# InterfacesB_SHIFTER_LEDS.net
KiCad netlist of a schematic drawn in Altium Designer
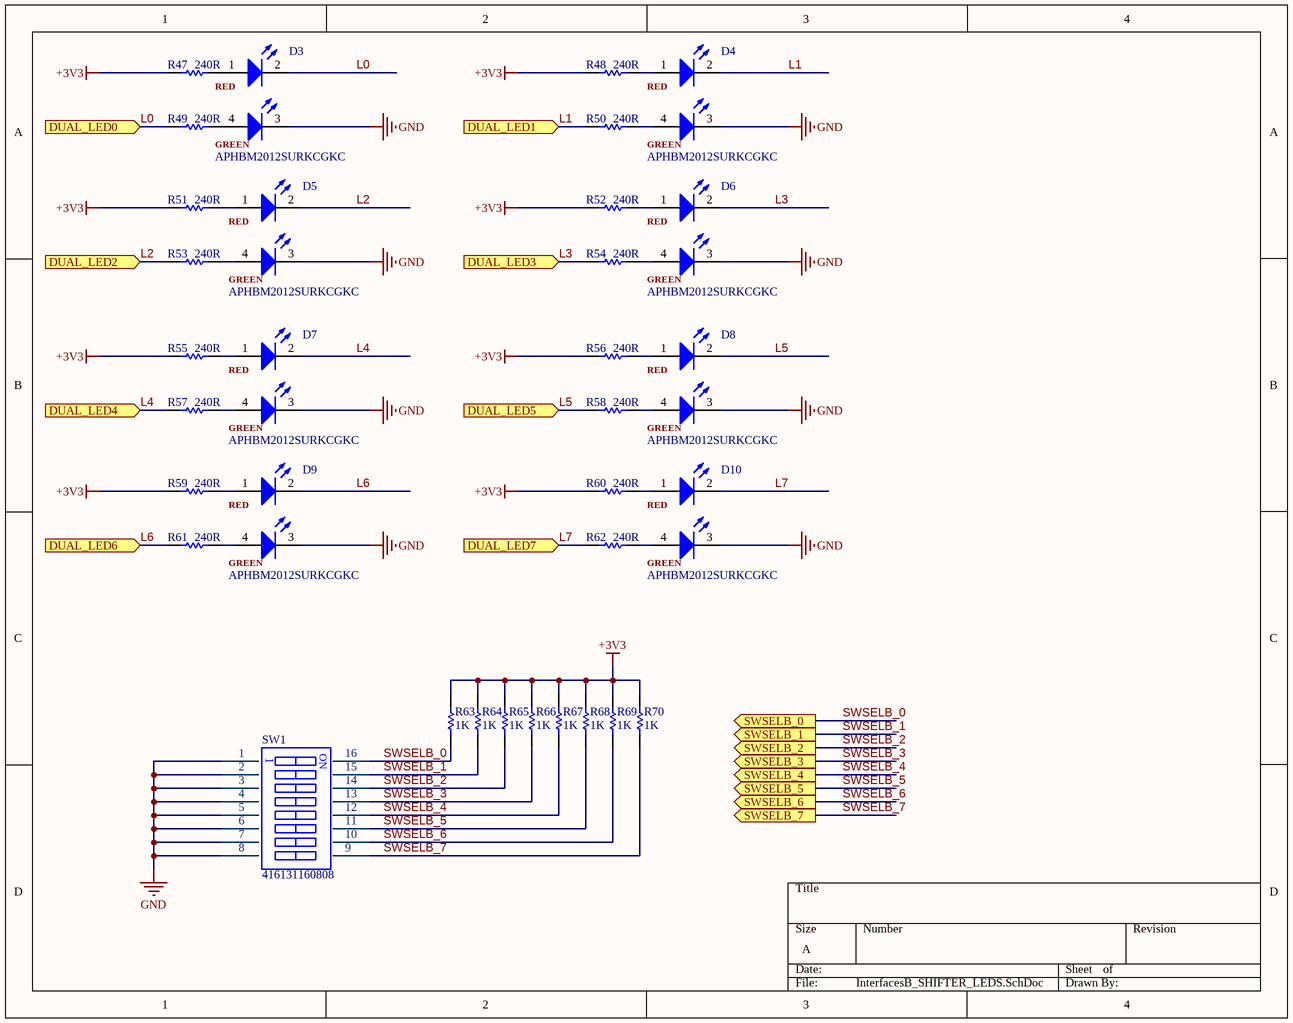
[diagram p0: InterfacesB_SHIFTER_LEDS.SchDoc]

(export (version "E")
  (design (tool "Eeschema 10.0.6"))
  (components
    (comp (ref "D3")
      (value "APHBM2012SURKCGKC")
      (footprint "APHBM2012SURKCGKC")
      (libsource (lib "AdapterLib") (part "APHBM2012SURKCGKC"))
    )
    (comp (ref "D4")
      (value "APHBM2012SURKCGKC")
      (footprint "APHBM2012SURKCGKC")
      (libsource (lib "AdapterLib") (part "APHBM2012SURKCGKC"))
    )
    (comp (ref "D5")
      (value "APHBM2012SURKCGKC")
      (footprint "APHBM2012SURKCGKC")
      (libsource (lib "AdapterLib") (part "APHBM2012SURKCGKC"))
    )
    (comp (ref "D6")
      (value "APHBM2012SURKCGKC")
      (footprint "APHBM2012SURKCGKC")
      (libsource (lib "AdapterLib") (part "APHBM2012SURKCGKC"))
    )
    (comp (ref "D7")
      (value "APHBM2012SURKCGKC")
      (footprint "APHBM2012SURKCGKC")
      (libsource (lib "AdapterLib") (part "APHBM2012SURKCGKC"))
    )
    (comp (ref "D8")
      (value "APHBM2012SURKCGKC")
      (footprint "APHBM2012SURKCGKC")
      (libsource (lib "AdapterLib") (part "APHBM2012SURKCGKC"))
    )
    (comp (ref "D9")
      (value "APHBM2012SURKCGKC")
      (footprint "APHBM2012SURKCGKC")
      (libsource (lib "AdapterLib") (part "APHBM2012SURKCGKC"))
    )
    (comp (ref "D10")
      (value "APHBM2012SURKCGKC")
      (footprint "APHBM2012SURKCGKC")
      (libsource (lib "AdapterLib") (part "APHBM2012SURKCGKC"))
    )
    (comp (ref "R47")
      (value "240R")
      (footprint "RES_0805")
      (fields (field (name "Comment") "RES_0805"))
      (libsource (lib "AdapterLib") (part "RES_0805"))
    )
    (comp (ref "R48")
      (value "240R")
      (footprint "RES_0805")
      (fields (field (name "Comment") "RES_0805"))
      (libsource (lib "AdapterLib") (part "RES_0805"))
    )
    (comp (ref "R49")
      (value "240R")
      (footprint "RES_0805")
      (fields (field (name "Comment") "RES_0805"))
      (libsource (lib "AdapterLib") (part "RES_0805"))
    )
    (comp (ref "R50")
      (value "240R")
      (footprint "RES_0805")
      (fields (field (name "Comment") "RES_0805"))
      (libsource (lib "AdapterLib") (part "RES_0805"))
    )
    (comp (ref "R51")
      (value "240R")
      (footprint "RES_0805")
      (fields (field (name "Comment") "RES_0805"))
      (libsource (lib "AdapterLib") (part "RES_0805"))
    )
    (comp (ref "R52")
      (value "240R")
      (footprint "RES_0805")
      (fields (field (name "Comment") "RES_0805"))
      (libsource (lib "AdapterLib") (part "RES_0805"))
    )
    (comp (ref "R53")
      (value "240R")
      (footprint "RES_0805")
      (fields (field (name "Comment") "RES_0805"))
      (libsource (lib "AdapterLib") (part "RES_0805"))
    )
    (comp (ref "R54")
      (value "240R")
      (footprint "RES_0805")
      (fields (field (name "Comment") "RES_0805"))
      (libsource (lib "AdapterLib") (part "RES_0805"))
    )
    (comp (ref "R55")
      (value "240R")
      (footprint "RES_0805")
      (fields (field (name "Comment") "RES_0805"))
      (libsource (lib "AdapterLib") (part "RES_0805"))
    )
    (comp (ref "R56")
      (value "240R")
      (footprint "RES_0805")
      (fields (field (name "Comment") "RES_0805"))
      (libsource (lib "AdapterLib") (part "RES_0805"))
    )
    (comp (ref "R57")
      (value "240R")
      (footprint "RES_0805")
      (fields (field (name "Comment") "RES_0805"))
      (libsource (lib "AdapterLib") (part "RES_0805"))
    )
    (comp (ref "R58")
      (value "240R")
      (footprint "RES_0805")
      (fields (field (name "Comment") "RES_0805"))
      (libsource (lib "AdapterLib") (part "RES_0805"))
    )
    (comp (ref "R59")
      (value "240R")
      (footprint "RES_0805")
      (fields (field (name "Comment") "RES_0805"))
      (libsource (lib "AdapterLib") (part "RES_0805"))
    )
    (comp (ref "R60")
      (value "240R")
      (footprint "RES_0805")
      (fields (field (name "Comment") "RES_0805"))
      (libsource (lib "AdapterLib") (part "RES_0805"))
    )
    (comp (ref "R61")
      (value "240R")
      (footprint "RES_0805")
      (fields (field (name "Comment") "RES_0805"))
      (libsource (lib "AdapterLib") (part "RES_0805"))
    )
    (comp (ref "R62")
      (value "240R")
      (footprint "RES_0805")
      (fields (field (name "Comment") "RES_0805"))
      (libsource (lib "AdapterLib") (part "RES_0805"))
    )
    (comp (ref "R63")
      (value "1K")
      (footprint "RES_0805")
      (fields (field (name "Comment") "RES_0805"))
      (libsource (lib "AdapterLib") (part "RES_0805"))
    )
    (comp (ref "R64")
      (value "1K")
      (footprint "RES_0805")
      (fields (field (name "Comment") "RES_0805"))
      (libsource (lib "AdapterLib") (part "RES_0805"))
    )
    (comp (ref "R65")
      (value "1K")
      (footprint "RES_0805")
      (fields (field (name "Comment") "RES_0805"))
      (libsource (lib "AdapterLib") (part "RES_0805"))
    )
    (comp (ref "R66")
      (value "1K")
      (footprint "RES_0805")
      (fields (field (name "Comment") "RES_0805"))
      (libsource (lib "AdapterLib") (part "RES_0805"))
    )
    (comp (ref "R67")
      (value "1K")
      (footprint "RES_0805")
      (fields (field (name "Comment") "RES_0805"))
      (libsource (lib "AdapterLib") (part "RES_0805"))
    )
    (comp (ref "R68")
      (value "1K")
      (footprint "RES_0805")
      (fields (field (name "Comment") "RES_0805"))
      (libsource (lib "AdapterLib") (part "RES_0805"))
    )
    (comp (ref "R69")
      (value "1K")
      (footprint "RES_0805")
      (fields (field (name "Comment") "RES_0805"))
      (libsource (lib "AdapterLib") (part "RES_0805"))
    )
    (comp (ref "R70")
      (value "1K")
      (footprint "RES_0805")
      (fields (field (name "Comment") "RES_0805"))
      (libsource (lib "AdapterLib") (part "RES_0805"))
    )
    (comp (ref "SW1")
      (value "416131160808")
      (footprint "416131160808")
      (description "8 POS DIP SW SMD")
      (libsource (lib "AdapterLib") (part "416131160808"))
    )
  )
  (nets
    (net (code "1") (name "+3V3") (class "Default")
      (node (ref "R47") (pin "2") (pinfunction "2_2") (pintype "passive"))
      (node (ref "R48") (pin "2") (pinfunction "2_2") (pintype "passive"))
      (node (ref "R51") (pin "2") (pinfunction "2_2") (pintype "passive"))
      (node (ref "R52") (pin "2") (pinfunction "2_2") (pintype "passive"))
      (node (ref "R55") (pin "2") (pinfunction "2_2") (pintype "passive"))
      (node (ref "R56") (pin "2") (pinfunction "2_2") (pintype "passive"))
      (node (ref "R59") (pin "2") (pinfunction "2_2") (pintype "passive"))
      (node (ref "R60") (pin "2") (pinfunction "2_2") (pintype "passive"))
      (node (ref "R63") (pin "2") (pinfunction "2_2") (pintype "passive"))
      (node (ref "R64") (pin "2") (pinfunction "2_2") (pintype "passive"))
      (node (ref "R65") (pin "2") (pinfunction "2_2") (pintype "passive"))
      (node (ref "R66") (pin "2") (pinfunction "2_2") (pintype "passive"))
      (node (ref "R67") (pin "2") (pinfunction "2_2") (pintype "passive"))
      (node (ref "R68") (pin "2") (pinfunction "2_2") (pintype "passive"))
      (node (ref "R69") (pin "2") (pinfunction "2_2") (pintype "passive"))
      (node (ref "R70") (pin "2") (pinfunction "2_2") (pintype "passive"))
    )
    (net (code "2") (name "/L0") (class "Default")
      (node (ref "D3") (pin "2") (pinfunction "2_2") (pintype "passive"))
      (node (ref "R49") (pin "2") (pinfunction "2_2") (pintype "passive"))
    )
    (net (code "3") (name "/L1") (class "Default")
      (node (ref "D4") (pin "2") (pinfunction "2_2") (pintype "passive"))
      (node (ref "R50") (pin "2") (pinfunction "2_2") (pintype "passive"))
    )
    (net (code "4") (name "/L2") (class "Default")
      (node (ref "D5") (pin "2") (pinfunction "2_2") (pintype "passive"))
      (node (ref "R53") (pin "2") (pinfunction "2_2") (pintype "passive"))
    )
    (net (code "5") (name "/L3") (class "Default")
      (node (ref "D6") (pin "2") (pinfunction "2_2") (pintype "passive"))
      (node (ref "R54") (pin "2") (pinfunction "2_2") (pintype "passive"))
    )
    (net (code "6") (name "/L4") (class "Default")
      (node (ref "D7") (pin "2") (pinfunction "2_2") (pintype "passive"))
      (node (ref "R57") (pin "2") (pinfunction "2_2") (pintype "passive"))
    )
    (net (code "7") (name "/L5") (class "Default")
      (node (ref "D8") (pin "2") (pinfunction "2_2") (pintype "passive"))
      (node (ref "R58") (pin "2") (pinfunction "2_2") (pintype "passive"))
    )
    (net (code "8") (name "/L6") (class "Default")
      (node (ref "D9") (pin "2") (pinfunction "2_2") (pintype "passive"))
      (node (ref "R61") (pin "2") (pinfunction "2_2") (pintype "passive"))
    )
    (net (code "9") (name "/L7") (class "Default")
      (node (ref "D10") (pin "2") (pinfunction "2_2") (pintype "passive"))
      (node (ref "R62") (pin "2") (pinfunction "2_2") (pintype "passive"))
    )
    (net (code "10") (name "/SWSELB_0") (class "Default")
      (node (ref "R63") (pin "1") (pinfunction "1_1") (pintype "passive"))
      (node (ref "SW1") (pin "16") (pintype "passive"))
    )
    (net (code "11") (name "/SWSELB_1") (class "Default")
      (node (ref "R64") (pin "1") (pinfunction "1_1") (pintype "passive"))
      (node (ref "SW1") (pin "15") (pintype "passive"))
    )
    (net (code "12") (name "/SWSELB_2") (class "Default")
      (node (ref "R65") (pin "1") (pinfunction "1_1") (pintype "passive"))
      (node (ref "SW1") (pin "14") (pintype "passive"))
    )
    (net (code "13") (name "/SWSELB_3") (class "Default")
      (node (ref "R66") (pin "1") (pinfunction "1_1") (pintype "passive"))
      (node (ref "SW1") (pin "13") (pintype "passive"))
    )
    (net (code "14") (name "/SWSELB_4") (class "Default")
      (node (ref "R67") (pin "1") (pinfunction "1_1") (pintype "passive"))
      (node (ref "SW1") (pin "12") (pintype "passive"))
    )
    (net (code "15") (name "/SWSELB_5") (class "Default")
      (node (ref "R68") (pin "1") (pinfunction "1_1") (pintype "passive"))
      (node (ref "SW1") (pin "11") (pintype "passive"))
    )
    (net (code "16") (name "/SWSELB_6") (class "Default")
      (node (ref "R69") (pin "1") (pinfunction "1_1") (pintype "passive"))
      (node (ref "SW1") (pin "10") (pintype "passive"))
    )
    (net (code "17") (name "/SWSELB_7") (class "Default")
      (node (ref "R70") (pin "1") (pinfunction "1_1") (pintype "passive"))
      (node (ref "SW1") (pin "9") (pintype "passive"))
    )
    (net (code "18") (name "GND") (class "Default")
      (node (ref "D10") (pin "3") (pinfunction "3_3") (pintype "passive"))
      (node (ref "D3") (pin "3") (pinfunction "3_3") (pintype "passive"))
      (node (ref "D4") (pin "3") (pinfunction "3_3") (pintype "passive"))
      (node (ref "D5") (pin "3") (pinfunction "3_3") (pintype "passive"))
      (node (ref "D6") (pin "3") (pinfunction "3_3") (pintype "passive"))
      (node (ref "D7") (pin "3") (pinfunction "3_3") (pintype "passive"))
      (node (ref "D8") (pin "3") (pinfunction "3_3") (pintype "passive"))
      (node (ref "D9") (pin "3") (pinfunction "3_3") (pintype "passive"))
      (node (ref "SW1") (pin "1") (pintype "passive"))
      (node (ref "SW1") (pin "2") (pintype "passive"))
      (node (ref "SW1") (pin "3") (pintype "passive"))
      (node (ref "SW1") (pin "4") (pintype "passive"))
      (node (ref "SW1") (pin "5") (pintype "passive"))
      (node (ref "SW1") (pin "6") (pintype "passive"))
      (node (ref "SW1") (pin "7") (pintype "passive"))
      (node (ref "SW1") (pin "8") (pintype "passive"))
    )
    (net (code "19") (name "Net-(D3-Pad1)") (class "Default")
      (node (ref "D3") (pin "1") (pinfunction "1_1") (pintype "passive"))
      (node (ref "R47") (pin "1") (pinfunction "1_1") (pintype "passive"))
    )
    (net (code "20") (name "Net-(D3-Pad4)") (class "Default")
      (node (ref "D3") (pin "4") (pinfunction "4_4") (pintype "passive"))
      (node (ref "R49") (pin "1") (pinfunction "1_1") (pintype "passive"))
    )
    (net (code "21") (name "Net-(D4-Pad1)") (class "Default")
      (node (ref "D4") (pin "1") (pinfunction "1_1") (pintype "passive"))
      (node (ref "R48") (pin "1") (pinfunction "1_1") (pintype "passive"))
    )
    (net (code "22") (name "Net-(D4-Pad4)") (class "Default")
      (node (ref "D4") (pin "4") (pinfunction "4_4") (pintype "passive"))
      (node (ref "R50") (pin "1") (pinfunction "1_1") (pintype "passive"))
    )
    (net (code "23") (name "Net-(D5-Pad1)") (class "Default")
      (node (ref "D5") (pin "1") (pinfunction "1_1") (pintype "passive"))
      (node (ref "R51") (pin "1") (pinfunction "1_1") (pintype "passive"))
    )
    (net (code "24") (name "Net-(D5-Pad4)") (class "Default")
      (node (ref "D5") (pin "4") (pinfunction "4_4") (pintype "passive"))
      (node (ref "R53") (pin "1") (pinfunction "1_1") (pintype "passive"))
    )
    (net (code "25") (name "Net-(D6-Pad1)") (class "Default")
      (node (ref "D6") (pin "1") (pinfunction "1_1") (pintype "passive"))
      (node (ref "R52") (pin "1") (pinfunction "1_1") (pintype "passive"))
    )
    (net (code "26") (name "Net-(D6-Pad4)") (class "Default")
      (node (ref "D6") (pin "4") (pinfunction "4_4") (pintype "passive"))
      (node (ref "R54") (pin "1") (pinfunction "1_1") (pintype "passive"))
    )
    (net (code "27") (name "Net-(D7-Pad1)") (class "Default")
      (node (ref "D7") (pin "1") (pinfunction "1_1") (pintype "passive"))
      (node (ref "R55") (pin "1") (pinfunction "1_1") (pintype "passive"))
    )
    (net (code "28") (name "Net-(D7-Pad4)") (class "Default")
      (node (ref "D7") (pin "4") (pinfunction "4_4") (pintype "passive"))
      (node (ref "R57") (pin "1") (pinfunction "1_1") (pintype "passive"))
    )
    (net (code "29") (name "Net-(D8-Pad1)") (class "Default")
      (node (ref "D8") (pin "1") (pinfunction "1_1") (pintype "passive"))
      (node (ref "R56") (pin "1") (pinfunction "1_1") (pintype "passive"))
    )
    (net (code "30") (name "Net-(D8-Pad4)") (class "Default")
      (node (ref "D8") (pin "4") (pinfunction "4_4") (pintype "passive"))
      (node (ref "R58") (pin "1") (pinfunction "1_1") (pintype "passive"))
    )
    (net (code "31") (name "Net-(D9-Pad1)") (class "Default")
      (node (ref "D9") (pin "1") (pinfunction "1_1") (pintype "passive"))
      (node (ref "R59") (pin "1") (pinfunction "1_1") (pintype "passive"))
    )
    (net (code "32") (name "Net-(D9-Pad4)") (class "Default")
      (node (ref "D9") (pin "4") (pinfunction "4_4") (pintype "passive"))
      (node (ref "R61") (pin "1") (pinfunction "1_1") (pintype "passive"))
    )
    (net (code "33") (name "Net-(D10-Pad1)") (class "Default")
      (node (ref "D10") (pin "1") (pinfunction "1_1") (pintype "passive"))
      (node (ref "R60") (pin "1") (pinfunction "1_1") (pintype "passive"))
    )
    (net (code "34") (name "Net-(D10-Pad4)") (class "Default")
      (node (ref "D10") (pin "4") (pinfunction "4_4") (pintype "passive"))
      (node (ref "R62") (pin "1") (pinfunction "1_1") (pintype "passive"))
    )
  )
)
